# TEST_USB.net
KiCad netlist of a schematic drawn in Altium Designer
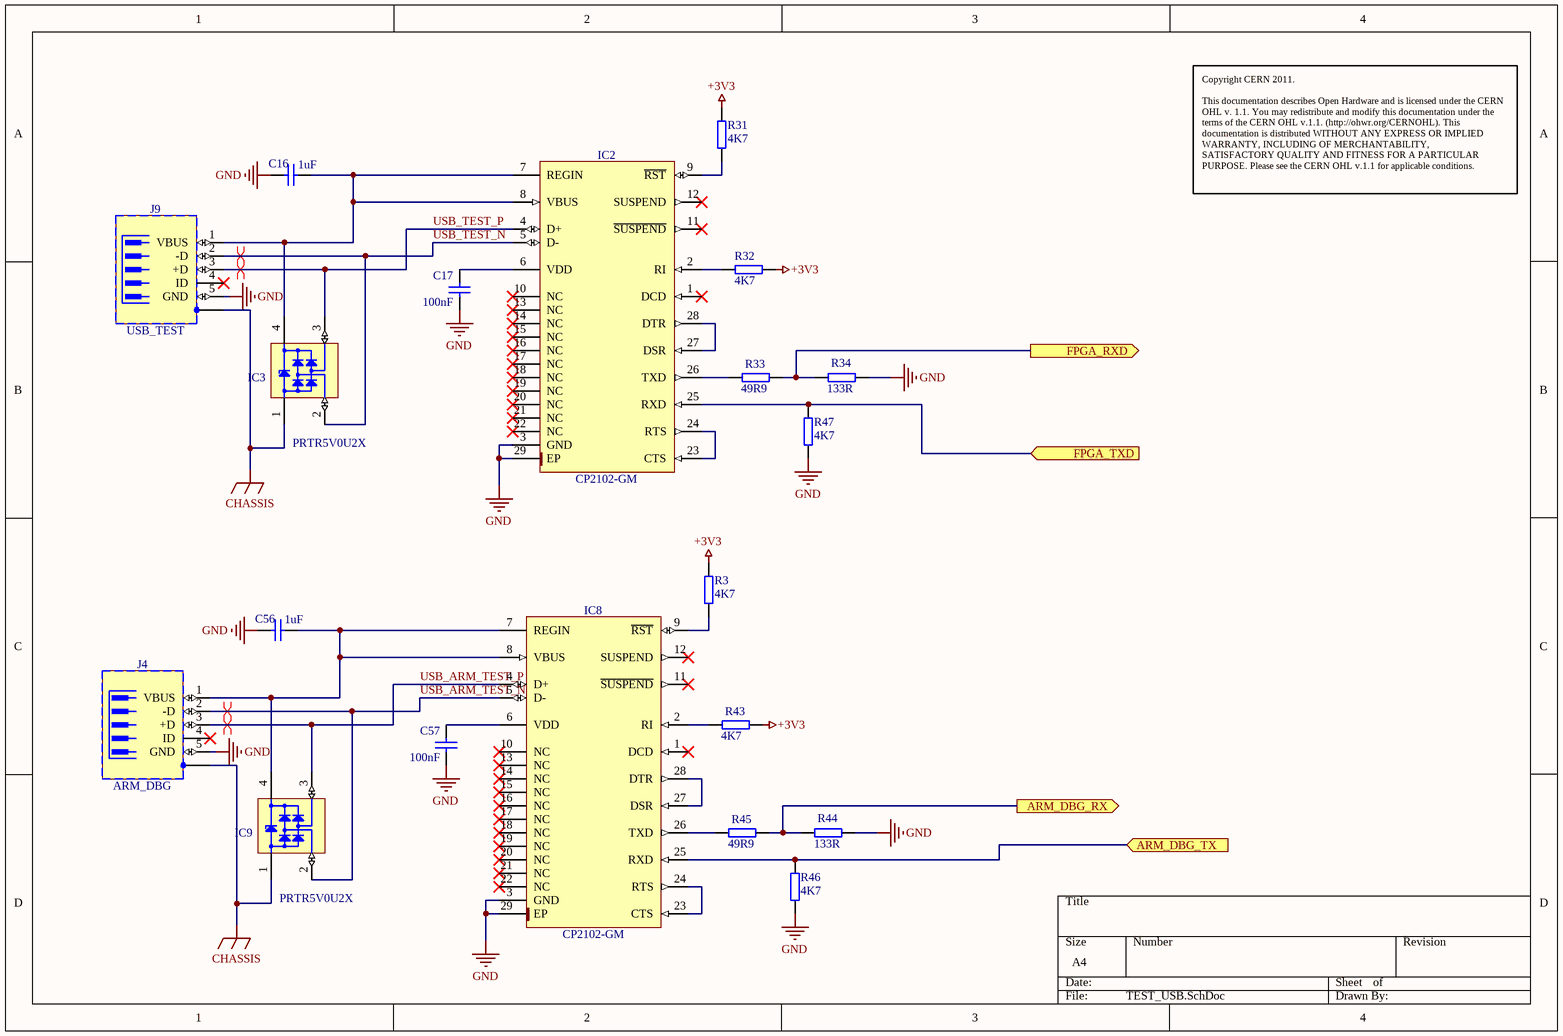
[diagram p0: TEST_USB.SchDoc]

(export (version "E")
  (design (tool "Eeschema 10.0.6"))
  (components
    (comp (ref "C16")
      (value "1uF")
      (footprint "CC1608-0603")
      (description "Capacitor")
      (fields
        (field (name "TOLERANCE") "±10%")
        (field (name "VOLTAGE") "25V")
        (field (name "PUBLISHER") "Altium Limited")
      )
      (libsource (lib "wr_switch") (part "Cap"))
    )
    (comp (ref "C17")
      (value "100nF")
      (footprint "CC1608-0603")
      (description "Capacitor")
      (fields
        (field (name "TOLERANCE") "±10%")
        (field (name "VOLTAGE") "16V")
        (field (name "PUBLISHER") "Altium Limited")
      )
      (libsource (lib "wr_switch") (part "Cap"))
    )
    (comp (ref "C56")
      (value "1uF")
      (footprint "CC1608-0603")
      (description "Capacitor")
      (fields
        (field (name "TOLERANCE") "±10%")
        (field (name "VOLTAGE") "25V")
        (field (name "PUBLISHER") "Altium Limited")
      )
      (libsource (lib "wr_switch") (part "Cap"))
    )
    (comp (ref "C57")
      (value "100nF")
      (footprint "CC1608-0603")
      (description "Capacitor")
      (fields
        (field (name "TOLERANCE") "±10%")
        (field (name "VOLTAGE") "16V")
        (field (name "PUBLISHER") "Altium Limited")
      )
      (libsource (lib "wr_switch") (part "Cap"))
    )
    (comp (ref "IC2")
      (value "CP2102-GM")
      (footprint "7S_WR:QFN50P500X500X100-29N-S335")
      (description "Single-Chip USB to UART Bridge")
      (fields (field (name "MANUFACTURER") "SILICON LABS") (field (name "AUTHOR") "CERN DEM JLC"))
      (libsource (lib "wr_switch") (part "CP2102-GM"))
    )
    (comp (ref "IC3")
      (value "PRTR5V0U2X")
      (footprint "7S_WR:SOT190P230X110-4N")
      (description "Ultra Low Capacitance Double Rail-to-Rail ESD Protection Diode")
      (fields
        (field (name "VOLTAGE") "5.5V")
        (field (name "MANUFACTURER") "PHILIPS NXP")
        (field (name "AUTHOR") "CERN DEM JLC")
      )
      (libsource (lib "wr_switch") (part "PRTR5V0U2X"))
    )
    (comp (ref "IC8")
      (value "CP2102-GM")
      (footprint "7S_WR:QFN50P500X500X100-29N-S335")
      (description "Single-Chip USB to UART Bridge")
      (fields (field (name "MANUFACTURER") "SILICON LABS") (field (name "AUTHOR") "CERN DEM JLC"))
      (libsource (lib "wr_switch") (part "CP2102-GM"))
    )
    (comp (ref "IC9")
      (value "PRTR5V0U2X")
      (footprint "7S_WR:SOT190P230X110-4N")
      (description "Ultra Low Capacitance Double Rail-to-Rail ESD Protection Diode")
      (fields
        (field (name "VOLTAGE") "5.5V")
        (field (name "MANUFACTURER") "PHILIPS NXP")
        (field (name "AUTHOR") "CERN DEM JLC")
      )
      (libsource (lib "wr_switch") (part "PRTR5V0U2X"))
    )
    (comp (ref "J4")
      (value "ARM_DBG")
      (footprint "7S_WR:TYCO_1734035-1")
      (description "5 Pin + 1 Shield Mini USB Type B Receptacle")
      (fields
        (field (name "PART NUMBER") "TYCO_1734035-1")
        (field (name "MANUFACTURER") "TYCO ELECTRONICS")
        (field (name "AUTHOR") "CERN DEM JLC")
      )
      (libsource (lib "wr_switch") (part "TYCO_1734035-1"))
    )
    (comp (ref "J9")
      (value "USB_TEST")
      (footprint "7S_WR:TYCO_1734035-1")
      (description "5 Pin + 1 Shield Mini USB Type B Receptacle")
      (fields
        (field (name "PART NUMBER") "TYCO_1734035-1")
        (field (name "MANUFACTURER") "TYCO ELECTRONICS")
        (field (name "AUTHOR") "CERN DEM JLC")
      )
      (libsource (lib "wr_switch") (part "TYCO_1734035-1"))
    )
    (comp (ref "R3")
      (value "4K7")
      (footprint "0603")
      (description "SMD Resistor")
      (fields (field (name "TOLERANCE") "±1%"))
      (libsource (lib "wr_switch") (part "RES_SMD"))
    )
    (comp (ref "R31")
      (value "4K7")
      (footprint "0603")
      (description "SMD Resistor")
      (fields (field (name "TOLERANCE") "±1%"))
      (libsource (lib "wr_switch") (part "RES_SMD"))
    )
    (comp (ref "R32")
      (value "4K7")
      (footprint "0603")
      (description "SMD Resistor")
      (fields (field (name "TOLERANCE") "±1%"))
      (libsource (lib "wr_switch") (part "RES_SMD"))
    )
    (comp (ref "R33")
      (value "49R9")
      (footprint "0603")
      (description "SMD Resistor")
      (fields (field (name "TOLERANCE") "±1%"))
      (libsource (lib "wr_switch") (part "RES_SMD"))
    )
    (comp (ref "R34")
      (value "133R")
      (footprint "0603")
      (description "SMD Resistor")
      (fields (field (name "TOLERANCE") "±1%"))
      (libsource (lib "wr_switch") (part "RES_SMD"))
    )
    (comp (ref "R43")
      (value "4K7")
      (footprint "0603")
      (description "SMD Resistor")
      (fields (field (name "TOLERANCE") "±1%"))
      (libsource (lib "wr_switch") (part "RES_SMD"))
    )
    (comp (ref "R44")
      (value "133R")
      (footprint "0603")
      (description "SMD Resistor")
      (fields (field (name "TOLERANCE") "±1%"))
      (libsource (lib "wr_switch") (part "RES_SMD"))
    )
    (comp (ref "R45")
      (value "49R9")
      (footprint "0603")
      (description "SMD Resistor")
      (fields (field (name "TOLERANCE") "±1%"))
      (libsource (lib "wr_switch") (part "RES_SMD"))
    )
    (comp (ref "R46")
      (value "4K7")
      (footprint "0603")
      (description "SMD Resistor")
      (fields (field (name "TOLERANCE") "±1%"))
      (libsource (lib "wr_switch") (part "RES_SMD"))
    )
    (comp (ref "R47")
      (value "4K7")
      (footprint "0603")
      (description "SMD Resistor")
      (fields (field (name "TOLERANCE") "±1%"))
      (libsource (lib "wr_switch") (part "RES_SMD"))
    )
  )
  (nets
    (net (code "1") (name "+3V3") (class "Default")
      (node (ref "R3") (pin "1") (pinfunction "1_1") (pintype "passive"))
      (node (ref "R31") (pin "1") (pinfunction "1_1") (pintype "passive"))
      (node (ref "R32") (pin "2") (pinfunction "2_2") (pintype "passive"))
      (node (ref "R43") (pin "2") (pinfunction "2_2") (pintype "passive"))
    )
    (net (code "2") (name "/ARM_DBG_RX") (class "Default")
      (node (ref "R44") (pin "1") (pinfunction "1_1") (pintype "passive"))
      (node (ref "R45") (pin "2") (pinfunction "2_2") (pintype "passive"))
    )
    (net (code "3") (name "/ARM_DBG_TX") (class "Default")
      (node (ref "IC8") (pin "25") (pinfunction "RXD_25") (pintype "input"))
      (node (ref "R46") (pin "1") (pinfunction "1_1") (pintype "passive"))
    )
    (net (code "4") (name "/FPGA_RXD") (class "Default")
      (node (ref "R33") (pin "2") (pinfunction "2_2") (pintype "passive"))
      (node (ref "R34") (pin "1") (pinfunction "1_1") (pintype "passive"))
    )
    (net (code "5") (name "/FPGA_TXD") (class "Default")
      (node (ref "IC2") (pin "25") (pinfunction "RXD_25") (pintype "input"))
      (node (ref "R47") (pin "1") (pinfunction "1_1") (pintype "passive"))
    )
    (net (code "6") (name "/USB_ARM_TEST_N") (class "Default")
      (node (ref "IC8") (pin "5") (pinfunction "D-_5") (pintype "bidirectional"))
      (node (ref "IC9") (pin "2") (pinfunction "I/O1_2") (pintype "bidirectional"))
      (node (ref "J4") (pin "2") (pinfunction "-D_2") (pintype "bidirectional"))
    )
    (net (code "7") (name "/USB_ARM_TEST_P") (class "Default")
      (node (ref "IC8") (pin "4") (pinfunction "D+_4") (pintype "bidirectional"))
      (node (ref "IC9") (pin "3") (pinfunction "I/O2_3") (pintype "bidirectional"))
      (node (ref "J4") (pin "3") (pinfunction "+D_3") (pintype "bidirectional"))
    )
    (net (code "8") (name "/USB_TEST_N") (class "Default")
      (node (ref "IC2") (pin "5") (pinfunction "D-_5") (pintype "bidirectional"))
      (node (ref "IC3") (pin "2") (pinfunction "I/O1_2") (pintype "bidirectional"))
      (node (ref "J9") (pin "2") (pinfunction "-D_2") (pintype "bidirectional"))
    )
    (net (code "9") (name "/USB_TEST_P") (class "Default")
      (node (ref "IC2") (pin "4") (pinfunction "D+_4") (pintype "bidirectional"))
      (node (ref "IC3") (pin "3") (pinfunction "I/O2_3") (pintype "bidirectional"))
      (node (ref "J9") (pin "3") (pinfunction "+D_3") (pintype "bidirectional"))
    )
    (net (code "10") (name "CHASSIS") (class "Default")
      (node (ref "IC3") (pin "1") (pinfunction "GND_1") (pintype "power_in"))
      (node (ref "IC9") (pin "1") (pinfunction "GND_1") (pintype "power_in"))
      (node (ref "J4") (pin "6") (pinfunction "SH_6") (pintype "power_in"))
      (node (ref "J9") (pin "6") (pinfunction "SH_6") (pintype "power_in"))
    )
    (net (code "11") (name "GND") (class "Default")
      (node (ref "C16") (pin "1") (pinfunction "1_1") (pintype "passive"))
      (node (ref "C17") (pin "2") (pinfunction "2_2") (pintype "passive"))
      (node (ref "C56") (pin "1") (pinfunction "1_1") (pintype "passive"))
      (node (ref "C57") (pin "2") (pinfunction "2_2") (pintype "passive"))
      (node (ref "IC2") (pin "29") (pinfunction "EP_29") (pintype "power_in"))
      (node (ref "IC2") (pin "3") (pinfunction "GND_3") (pintype "power_in"))
      (node (ref "IC8") (pin "29") (pinfunction "EP_29") (pintype "power_in"))
      (node (ref "IC8") (pin "3") (pinfunction "GND_3") (pintype "power_in"))
      (node (ref "J4") (pin "5") (pinfunction "GND_5") (pintype "bidirectional"))
      (node (ref "J9") (pin "5") (pinfunction "GND_5") (pintype "bidirectional"))
      (node (ref "R34") (pin "2") (pinfunction "2_2") (pintype "passive"))
      (node (ref "R44") (pin "2") (pinfunction "2_2") (pintype "passive"))
      (node (ref "R46") (pin "2") (pinfunction "2_2") (pintype "passive"))
      (node (ref "R47") (pin "2") (pinfunction "2_2") (pintype "passive"))
    )
    (net (code "12") (name "Net-(IC2-CTS)") (class "Default")
      (node (ref "IC2") (pin "23") (pinfunction "CTS_23") (pintype "input"))
      (node (ref "IC2") (pin "24") (pinfunction "RTS_24") (pintype "output"))
    )
    (net (code "13") (name "Net-(IC2-DSR)") (class "Default")
      (node (ref "IC2") (pin "27") (pinfunction "DSR_27") (pintype "input"))
      (node (ref "IC2") (pin "28") (pinfunction "DTR_28") (pintype "output"))
    )
    (net (code "14") (name "Net-(IC2-REGIN)") (class "Default")
      (node (ref "C16") (pin "2") (pinfunction "2_2") (pintype "passive"))
      (node (ref "IC2") (pin "7") (pinfunction "REGIN_7") (pintype "power_in"))
      (node (ref "IC2") (pin "8") (pinfunction "VBUS_8") (pintype "input"))
      (node (ref "IC3") (pin "4") (pinfunction "VCC_4") (pintype "power_in"))
      (node (ref "J9") (pin "1") (pinfunction "VBUS_1") (pintype "bidirectional"))
    )
    (net (code "15") (name "Net-(IC2-RI)") (class "Default")
      (node (ref "IC2") (pin "2") (pinfunction "RI_2") (pintype "input"))
      (node (ref "R32") (pin "1") (pinfunction "1_1") (pintype "passive"))
    )
    (net (code "16") (name "Net-(IC2-TXD)") (class "Default")
      (node (ref "IC2") (pin "26") (pinfunction "TXD_26") (pintype "output"))
      (node (ref "R33") (pin "1") (pinfunction "1_1") (pintype "passive"))
    )
    (net (code "17") (name "Net-(IC2-VDD)") (class "Default")
      (node (ref "C17") (pin "1") (pinfunction "1_1") (pintype "passive"))
      (node (ref "IC2") (pin "6") (pinfunction "VDD_6") (pintype "power_in"))
    )
    (net (code "18") (name "Net-(IC2-~{RST})") (class "Default")
      (node (ref "IC2") (pin "9") (pinfunction "~{RST}_9") (pintype "bidirectional"))
      (node (ref "R31") (pin "2") (pinfunction "2_2") (pintype "passive"))
    )
    (net (code "19") (name "Net-(IC8-CTS)") (class "Default")
      (node (ref "IC8") (pin "23") (pinfunction "CTS_23") (pintype "input"))
      (node (ref "IC8") (pin "24") (pinfunction "RTS_24") (pintype "output"))
    )
    (net (code "20") (name "Net-(IC8-DSR)") (class "Default")
      (node (ref "IC8") (pin "27") (pinfunction "DSR_27") (pintype "input"))
      (node (ref "IC8") (pin "28") (pinfunction "DTR_28") (pintype "output"))
    )
    (net (code "21") (name "Net-(IC8-REGIN)") (class "Default")
      (node (ref "C56") (pin "2") (pinfunction "2_2") (pintype "passive"))
      (node (ref "IC8") (pin "7") (pinfunction "REGIN_7") (pintype "power_in"))
      (node (ref "IC8") (pin "8") (pinfunction "VBUS_8") (pintype "input"))
      (node (ref "IC9") (pin "4") (pinfunction "VCC_4") (pintype "power_in"))
      (node (ref "J4") (pin "1") (pinfunction "VBUS_1") (pintype "bidirectional"))
    )
    (net (code "22") (name "Net-(IC8-RI)") (class "Default")
      (node (ref "IC8") (pin "2") (pinfunction "RI_2") (pintype "input"))
      (node (ref "R43") (pin "1") (pinfunction "1_1") (pintype "passive"))
    )
    (net (code "23") (name "Net-(IC8-TXD)") (class "Default")
      (node (ref "IC8") (pin "26") (pinfunction "TXD_26") (pintype "output"))
      (node (ref "R45") (pin "1") (pinfunction "1_1") (pintype "passive"))
    )
    (net (code "24") (name "Net-(IC8-VDD)") (class "Default")
      (node (ref "C57") (pin "1") (pinfunction "1_1") (pintype "passive"))
      (node (ref "IC8") (pin "6") (pinfunction "VDD_6") (pintype "power_in"))
    )
    (net (code "25") (name "Net-(IC8-~{RST})") (class "Default")
      (node (ref "IC8") (pin "9") (pinfunction "~{RST}_9") (pintype "bidirectional"))
      (node (ref "R3") (pin "2") (pinfunction "2_2") (pintype "passive"))
    )
    (net (code "26") (name "unconnected-(IC2-DCD-Pad1)") (class "Default")
      (node (ref "IC2") (pin "1") (pinfunction "DCD_1") (pintype "input+no_connect"))
    )
    (net (code "27") (name "unconnected-(IC2-NC-Pad10)") (class "Default")
      (node (ref "IC2") (pin "10") (pinfunction "NC_10") (pintype "passive+no_connect"))
    )
    (net (code "28") (name "unconnected-(IC2-NC-Pad13)") (class "Default")
      (node (ref "IC2") (pin "13") (pinfunction "NC_13") (pintype "passive+no_connect"))
    )
    (net (code "29") (name "unconnected-(IC2-NC-Pad14)") (class "Default")
      (node (ref "IC2") (pin "14") (pinfunction "NC_14") (pintype "passive+no_connect"))
    )
    (net (code "30") (name "unconnected-(IC2-NC-Pad15)") (class "Default")
      (node (ref "IC2") (pin "15") (pinfunction "NC_15") (pintype "passive+no_connect"))
    )
    (net (code "31") (name "unconnected-(IC2-NC-Pad16)") (class "Default")
      (node (ref "IC2") (pin "16") (pinfunction "NC_16") (pintype "passive+no_connect"))
    )
    (net (code "32") (name "unconnected-(IC2-NC-Pad17)") (class "Default")
      (node (ref "IC2") (pin "17") (pinfunction "NC_17") (pintype "passive+no_connect"))
    )
    (net (code "33") (name "unconnected-(IC2-NC-Pad18)") (class "Default")
      (node (ref "IC2") (pin "18") (pinfunction "NC_18") (pintype "passive+no_connect"))
    )
    (net (code "34") (name "unconnected-(IC2-NC-Pad19)") (class "Default")
      (node (ref "IC2") (pin "19") (pinfunction "NC_19") (pintype "passive+no_connect"))
    )
    (net (code "35") (name "unconnected-(IC2-NC-Pad20)") (class "Default")
      (node (ref "IC2") (pin "20") (pinfunction "NC_20") (pintype "passive+no_connect"))
    )
    (net (code "36") (name "unconnected-(IC2-NC-Pad21)") (class "Default")
      (node (ref "IC2") (pin "21") (pinfunction "NC_21") (pintype "passive+no_connect"))
    )
    (net (code "37") (name "unconnected-(IC2-NC-Pad22)") (class "Default")
      (node (ref "IC2") (pin "22") (pinfunction "NC_22") (pintype "passive+no_connect"))
    )
    (net (code "38") (name "unconnected-(IC2-SUSPEND-Pad12)") (class "Default")
      (node (ref "IC2") (pin "12") (pinfunction "SUSPEND_12") (pintype "output+no_connect"))
    )
    (net (code "39") (name "unconnected-(IC2-~{SUSPEND}-Pad11)") (class "Default")
      (node (ref "IC2") (pin "11") (pinfunction "~{SUSPEND}_11") (pintype "output+no_connect"))
    )
    (net (code "40") (name "unconnected-(IC8-DCD-Pad1)") (class "Default")
      (node (ref "IC8") (pin "1") (pinfunction "DCD_1") (pintype "input+no_connect"))
    )
    (net (code "41") (name "unconnected-(IC8-NC-Pad10)") (class "Default")
      (node (ref "IC8") (pin "10") (pinfunction "NC_10") (pintype "passive+no_connect"))
    )
    (net (code "42") (name "unconnected-(IC8-NC-Pad13)") (class "Default")
      (node (ref "IC8") (pin "13") (pinfunction "NC_13") (pintype "passive+no_connect"))
    )
    (net (code "43") (name "unconnected-(IC8-NC-Pad14)") (class "Default")
      (node (ref "IC8") (pin "14") (pinfunction "NC_14") (pintype "passive+no_connect"))
    )
    (net (code "44") (name "unconnected-(IC8-NC-Pad15)") (class "Default")
      (node (ref "IC8") (pin "15") (pinfunction "NC_15") (pintype "passive+no_connect"))
    )
    (net (code "45") (name "unconnected-(IC8-NC-Pad16)") (class "Default")
      (node (ref "IC8") (pin "16") (pinfunction "NC_16") (pintype "passive+no_connect"))
    )
    (net (code "46") (name "unconnected-(IC8-NC-Pad17)") (class "Default")
      (node (ref "IC8") (pin "17") (pinfunction "NC_17") (pintype "passive+no_connect"))
    )
    (net (code "47") (name "unconnected-(IC8-NC-Pad18)") (class "Default")
      (node (ref "IC8") (pin "18") (pinfunction "NC_18") (pintype "passive+no_connect"))
    )
    (net (code "48") (name "unconnected-(IC8-NC-Pad19)") (class "Default")
      (node (ref "IC8") (pin "19") (pinfunction "NC_19") (pintype "passive+no_connect"))
    )
    (net (code "49") (name "unconnected-(IC8-NC-Pad20)") (class "Default")
      (node (ref "IC8") (pin "20") (pinfunction "NC_20") (pintype "passive+no_connect"))
    )
    (net (code "50") (name "unconnected-(IC8-NC-Pad21)") (class "Default")
      (node (ref "IC8") (pin "21") (pinfunction "NC_21") (pintype "passive+no_connect"))
    )
    (net (code "51") (name "unconnected-(IC8-NC-Pad22)") (class "Default")
      (node (ref "IC8") (pin "22") (pinfunction "NC_22") (pintype "passive+no_connect"))
    )
    (net (code "52") (name "unconnected-(IC8-SUSPEND-Pad12)") (class "Default")
      (node (ref "IC8") (pin "12") (pinfunction "SUSPEND_12") (pintype "output+no_connect"))
    )
    (net (code "53") (name "unconnected-(IC8-~{SUSPEND}-Pad11)") (class "Default")
      (node (ref "IC8") (pin "11") (pinfunction "~{SUSPEND}_11") (pintype "output+no_connect"))
    )
    (net (code "54") (name "unconnected-(J4-ID-Pad4)") (class "Default")
      (node (ref "J4") (pin "4") (pinfunction "ID_4") (pintype "passive+no_connect"))
    )
    (net (code "55") (name "unconnected-(J9-ID-Pad4)") (class "Default")
      (node (ref "J9") (pin "4") (pinfunction "ID_4") (pintype "passive+no_connect"))
    )
  )
)
